# SCH_shield_test_2024-03-10.net
KiCad netlist of a schematic drawn in EasyEDA
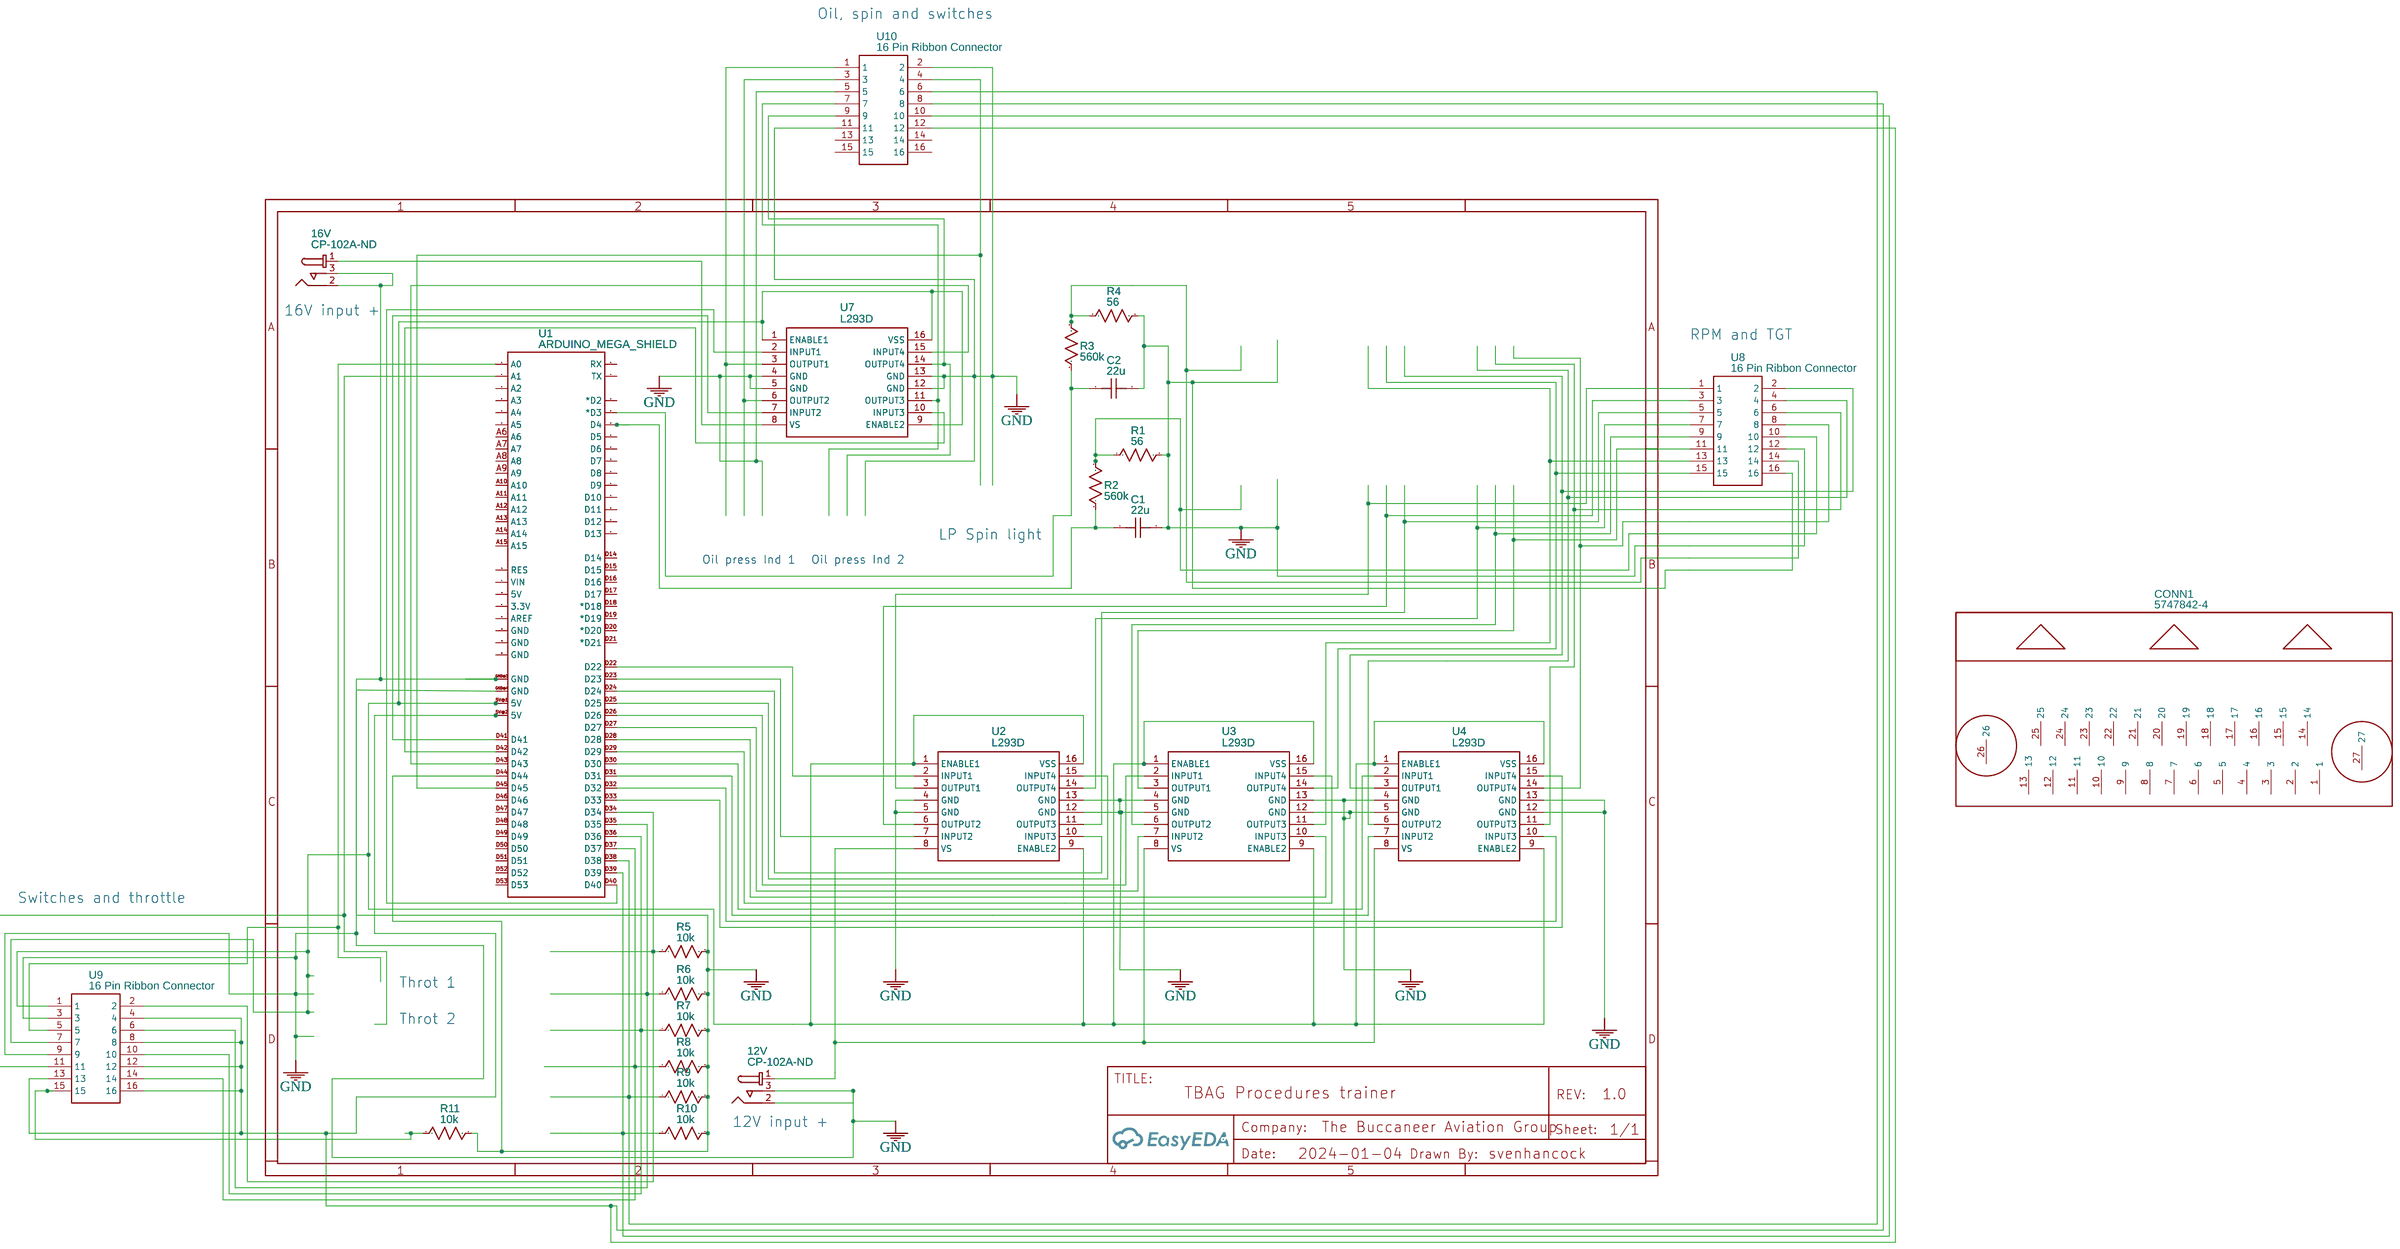
[diagram p0: schematic sheet]

(export (version "E")
  (design (tool "Eeschema 10.0.6"))
  (components
    (comp (ref "12V") (value "CP-102A-ND") (libsource (lib "") (part "CP-102A-ND")))
    (comp (ref "16V") (value "CP-102A-ND") (libsource (lib "") (part "CP-102A-ND_1")))
    (comp (ref "C1") (value "22u") (libsource (lib "") (part "C_0603_US")))
    (comp (ref "C2") (value "22u") (libsource (lib "") (part "C_0603_US")))
    (comp (ref "CONN1") (value "5747842-4") (libsource (lib "") (part "5747842-4")))
    (comp (ref "R1") (value "56") (libsource (lib "") (part "R_0603_US_1")))
    (comp (ref "R2") (value "560k") (libsource (lib "") (part "R_0603_US")))
    (comp (ref "R3") (value "560k") (libsource (lib "") (part "R_0603_US")))
    (comp (ref "R4") (value "56") (libsource (lib "") (part "R_0603_US_1")))
    (comp (ref "R5") (value "10k") (libsource (lib "") (part "R_0603_US_1")))
    (comp (ref "R6") (value "10k") (libsource (lib "") (part "R_0603_US_1")))
    (comp (ref "R7") (value "10k") (libsource (lib "") (part "R_0603_US_1")))
    (comp (ref "R8") (value "10k") (libsource (lib "") (part "R_0603_US_1")))
    (comp (ref "R9") (value "10k") (libsource (lib "") (part "R_0603_US_1")))
    (comp (ref "R10") (value "10k") (libsource (lib "") (part "R_0603_US_1")))
    (comp (ref "R11") (value "10k") (libsource (lib "") (part "R_0603_US_1")))
    (comp (ref "U1") (value "ARDUINO_MEGA_SHIELD") (libsource (lib "") (part "ARDUINO_MEGA_SHIELD")))
    (comp (ref "U2")
      (value "L293D")
      (fields (field (name "Manufacturer") "ST(意法半导体)"))
      (libsource (lib "") (part "L293D"))
    )
    (comp (ref "U3")
      (value "L293D")
      (fields (field (name "Manufacturer") "ST(意法半导体)"))
      (libsource (lib "") (part "L293D"))
    )
    (comp (ref "U4")
      (value "L293D")
      (fields (field (name "Manufacturer") "ST(意法半导体)"))
      (libsource (lib "") (part "L293D"))
    )
    (comp (ref "U7")
      (value "L293D")
      (fields (field (name "Manufacturer") "ST(意法半导体)"))
      (libsource (lib "") (part "L293D"))
    )
    (comp (ref "U8") (value "16 Pin Ribbon Connector") (libsource (lib "") (part "16 Pin Ribbon Connector")))
    (comp (ref "U9") (value "16 Pin Ribbon Connector") (libsource (lib "") (part "16 Pin Ribbon Connector")))
    (comp (ref "U10") (value "16 Pin Ribbon Connector") (libsource (lib "") (part "16 Pin Ribbon Connector")))
  )
  (nets
    (net (code "1") (name "GND") (class "Default")
      (node (ref "12V") (pin "2") (pintype "unspecified"))
      (node (ref "12V") (pin "3") (pintype "unspecified"))
      (node (ref "16V") (pin "2") (pintype "unspecified"))
      (node (ref "16V") (pin "3") (pintype "unspecified"))
      (node (ref "C1") (pin "2") (pinfunction "2_2") (pintype "unspecified"))
      (node (ref "C2") (pin "2") (pinfunction "2_2") (pintype "unspecified"))
      (node (ref "R1") (pin "2") (pinfunction "2_2") (pintype "unspecified"))
      (node (ref "R10") (pin "2") (pinfunction "2_2") (pintype "unspecified"))
      (node (ref "R11") (pin "2") (pinfunction "2_2") (pintype "unspecified"))
      (node (ref "R4") (pin "2") (pinfunction "2_2") (pintype "unspecified"))
      (node (ref "R5") (pin "2") (pinfunction "2_2") (pintype "unspecified"))
      (node (ref "R6") (pin "2") (pinfunction "2_2") (pintype "unspecified"))
      (node (ref "R7") (pin "2") (pinfunction "2_2") (pintype "unspecified"))
      (node (ref "R8") (pin "2") (pinfunction "2_2") (pintype "unspecified"))
      (node (ref "R9") (pin "2") (pinfunction "2_2") (pintype "unspecified"))
      (node (ref "U1") (pin "D44") (pinfunction "D44_D44") (pintype "unspecified"))
      (node (ref "U1") (pin "GND@3") (pinfunction "GND_GND@3") (pintype "unspecified"))
      (node (ref "U10") (pin "11") (pinfunction "11_11") (pintype "unspecified"))
      (node (ref "U10") (pin "2") (pinfunction "2_2") (pintype "unspecified"))
      (node (ref "U10") (pin "5") (pinfunction "5_5") (pintype "unspecified"))
      (node (ref "U2") (pin "12") (pinfunction "GND_12") (pintype "unspecified"))
      (node (ref "U2") (pin "13") (pinfunction "GND_13") (pintype "unspecified"))
      (node (ref "U2") (pin "4") (pinfunction "GND_4") (pintype "unspecified"))
      (node (ref "U2") (pin "5") (pinfunction "GND_5") (pintype "unspecified"))
      (node (ref "U3") (pin "12") (pinfunction "GND_12") (pintype "unspecified"))
      (node (ref "U3") (pin "13") (pinfunction "GND_13") (pintype "unspecified"))
      (node (ref "U3") (pin "4") (pinfunction "GND_4") (pintype "unspecified"))
      (node (ref "U3") (pin "5") (pinfunction "GND_5") (pintype "unspecified"))
      (node (ref "U4") (pin "12") (pinfunction "GND_12") (pintype "unspecified"))
      (node (ref "U4") (pin "13") (pinfunction "GND_13") (pintype "unspecified"))
      (node (ref "U4") (pin "4") (pinfunction "GND_4") (pintype "unspecified"))
      (node (ref "U4") (pin "5") (pinfunction "GND_5") (pintype "unspecified"))
      (node (ref "U7") (pin "12") (pinfunction "GND_12") (pintype "unspecified"))
      (node (ref "U7") (pin "13") (pinfunction "GND_13") (pintype "unspecified"))
      (node (ref "U7") (pin "4") (pinfunction "GND_4") (pintype "unspecified"))
      (node (ref "U7") (pin "5") (pinfunction "GND_5") (pintype "unspecified"))
      (node (ref "U8") (pin "12") (pinfunction "12_12") (pintype "unspecified"))
      (node (ref "U8") (pin "16") (pinfunction "16_16") (pintype "unspecified"))
      (node (ref "U9") (pin "3") (pinfunction "3_3") (pintype "unspecified"))
      (node (ref "U9") (pin "9") (pinfunction "9_9") (pintype "unspecified"))
    )
    (net (code "2") (name "Net-(C1-Pad1)") (class "Default")
      (node (ref "C1") (pin "1") (pinfunction "1_1") (pintype "unspecified"))
      (node (ref "R2") (pin "1") (pinfunction "1_1") (pintype "unspecified"))
      (node (ref "U1") (pin "D4") (pinfunction "D4_D4") (pintype "unspecified"))
    )
    (net (code "3") (name "Net-(R1-Pad1)") (class "Default")
      (node (ref "R1") (pin "1") (pinfunction "1_1") (pintype "unspecified"))
      (node (ref "R2") (pin "2") (pinfunction "2_2") (pintype "unspecified"))
      (node (ref "U8") (pin "10") (pinfunction "10_10") (pintype "unspecified"))
    )
    (net (code "4") (name "Net-(R3-Pad2)") (class "Default")
      (node (ref "R3") (pin "2") (pinfunction "2_2") (pintype "unspecified"))
      (node (ref "R4") (pin "1") (pinfunction "1_1") (pintype "unspecified"))
      (node (ref "U8") (pin "14") (pinfunction "14_14") (pintype "unspecified"))
    )
    (net (code "5") (name "Net-(R5-Pad1)") (class "Default")
      (node (ref "R5") (pin "1") (pinfunction "1_1") (pintype "unspecified"))
      (node (ref "U1") (pin "D34") (pinfunction "D34_D34") (pintype "unspecified"))
      (node (ref "U9") (pin "2") (pinfunction "2_2") (pintype "unspecified"))
    )
    (net (code "6") (name "Net-(R6-Pad1)") (class "Default")
      (node (ref "R6") (pin "1") (pinfunction "1_1") (pintype "unspecified"))
      (node (ref "U1") (pin "D35") (pinfunction "D35_D35") (pintype "unspecified"))
      (node (ref "U9") (pin "6") (pinfunction "6_6") (pintype "unspecified"))
    )
    (net (code "7") (name "Net-(R7-Pad1)") (class "Default")
      (node (ref "R7") (pin "1") (pinfunction "1_1") (pintype "unspecified"))
      (node (ref "U1") (pin "D36") (pinfunction "D36_D36") (pintype "unspecified"))
      (node (ref "U9") (pin "10") (pinfunction "10_10") (pintype "unspecified"))
    )
    (net (code "8") (name "Net-(R8-Pad1)") (class "Default")
      (node (ref "R8") (pin "1") (pinfunction "1_1") (pintype "unspecified"))
      (node (ref "U1") (pin "D37") (pinfunction "D37_D37") (pintype "unspecified"))
      (node (ref "U9") (pin "14") (pinfunction "14_14") (pintype "unspecified"))
    )
    (net (code "9") (name "Net-(R9-Pad1)") (class "Default")
      (node (ref "R9") (pin "1") (pinfunction "1_1") (pintype "unspecified"))
      (node (ref "U1") (pin "D38") (pinfunction "D38_D38") (pintype "unspecified"))
      (node (ref "U10") (pin "6") (pinfunction "6_6") (pintype "unspecified"))
    )
    (net (code "10") (name "Net-(R10-Pad1)") (class "Default")
      (node (ref "R10") (pin "1") (pinfunction "1_1") (pintype "unspecified"))
      (node (ref "U1") (pin "D39") (pinfunction "D39_D39") (pintype "unspecified"))
      (node (ref "U10") (pin "10") (pinfunction "10_10") (pintype "unspecified"))
    )
    (net (code "11") (name "Net-(R11-Pad1)") (class "Default")
      (node (ref "R11") (pin "1") (pinfunction "1_1") (pintype "unspecified"))
      (node (ref "U9") (pin "15") (pinfunction "15_15") (pintype "unspecified"))
    )
    (net (code "12") (name "Net-(U1-*D3)") (class "Default")
      (node (ref "C2") (pin "1") (pinfunction "1_1") (pintype "unspecified"))
      (node (ref "R3") (pin "1") (pinfunction "1_1") (pintype "unspecified"))
      (node (ref "U1") (pin "D3") (pinfunction "*D3_D3") (pintype "unspecified"))
    )
    (net (code "13") (name "Net-(U1-5V-Pad5V@2)") (class "Default")
      (node (ref "U1") (pin "5V@2") (pinfunction "5V_5V@2") (pintype "unspecified"))
      (node (ref "U10") (pin "12") (pinfunction "12_12") (pintype "unspecified"))
      (node (ref "U10") (pin "8") (pinfunction "8_8") (pintype "unspecified"))
      (node (ref "U9") (pin "12") (pinfunction "12_12") (pintype "unspecified"))
      (node (ref "U9") (pin "13") (pinfunction "13_13") (pintype "unspecified"))
      (node (ref "U9") (pin "16") (pinfunction "16_16") (pintype "unspecified"))
      (node (ref "U9") (pin "4") (pinfunction "4_4") (pintype "unspecified"))
      (node (ref "U9") (pin "8") (pinfunction "8_8") (pintype "unspecified"))
    )
    (net (code "14") (name "Net-(U1-PadA0)") (class "Default")
      (node (ref "U1") (pin "A0") (pinfunction "A0_A0") (pintype "unspecified"))
      (node (ref "U9") (pin "5") (pinfunction "5_5") (pintype "unspecified"))
    )
    (net (code "15") (name "Net-(U1-PadA1)") (class "Default")
      (node (ref "U1") (pin "A1") (pinfunction "A1_A1") (pintype "unspecified"))
      (node (ref "U9") (pin "11") (pinfunction "11_11") (pintype "unspecified"))
    )
    (net (code "16") (name "Net-(U1-PadD45)") (class "Default")
      (node (ref "U1") (pin "D45") (pinfunction "D45_D45") (pintype "unspecified"))
      (node (ref "U10") (pin "4") (pinfunction "4_4") (pintype "unspecified"))
    )
    (net (code "17") (name "Net-(U2-ENABLE1)") (class "Default")
      (node (ref "U1") (pin "5V@1") (pinfunction "5V_5V@1") (pintype "unspecified"))
      (node (ref "U2") (pin "1") (pinfunction "ENABLE1_1") (pintype "unspecified"))
      (node (ref "U2") (pin "16") (pinfunction "VSS_16") (pintype "unspecified"))
      (node (ref "U2") (pin "9") (pinfunction "ENABLE2_9") (pintype "unspecified"))
      (node (ref "U3") (pin "1") (pinfunction "ENABLE1_1") (pintype "unspecified"))
      (node (ref "U3") (pin "16") (pinfunction "VSS_16") (pintype "unspecified"))
      (node (ref "U3") (pin "9") (pinfunction "ENABLE2_9") (pintype "unspecified"))
      (node (ref "U4") (pin "1") (pinfunction "ENABLE1_1") (pintype "unspecified"))
      (node (ref "U4") (pin "16") (pinfunction "VSS_16") (pintype "unspecified"))
      (node (ref "U4") (pin "9") (pinfunction "ENABLE2_9") (pintype "unspecified"))
      (node (ref "U7") (pin "1") (pinfunction "ENABLE1_1") (pintype "unspecified"))
      (node (ref "U7") (pin "16") (pinfunction "VSS_16") (pintype "unspecified"))
      (node (ref "U7") (pin "9") (pinfunction "ENABLE2_9") (pintype "unspecified"))
      (node (ref "U9") (pin "1") (pinfunction "1_1") (pintype "unspecified"))
      (node (ref "U9") (pin "7") (pinfunction "7_7") (pintype "unspecified"))
    )
    (net (code "18") (name "Net-(U2-INPUT1)") (class "Default")
      (node (ref "U1") (pin "D22") (pinfunction "D22_D22") (pintype "unspecified"))
      (node (ref "U2") (pin "2") (pinfunction "INPUT1_2") (pintype "unspecified"))
    )
    (net (code "19") (name "Net-(U2-INPUT2)") (class "Default")
      (node (ref "U1") (pin "D23") (pinfunction "D23_D23") (pintype "unspecified"))
      (node (ref "U2") (pin "7") (pinfunction "INPUT2_7") (pintype "unspecified"))
    )
    (net (code "20") (name "Net-(U2-INPUT3)") (class "Default")
      (node (ref "U1") (pin "D24") (pinfunction "D24_D24") (pintype "unspecified"))
      (node (ref "U2") (pin "10") (pinfunction "INPUT3_10") (pintype "unspecified"))
    )
    (net (code "21") (name "Net-(U2-INPUT4)") (class "Default")
      (node (ref "U1") (pin "D25") (pinfunction "D25_D25") (pintype "unspecified"))
      (node (ref "U2") (pin "15") (pinfunction "INPUT4_15") (pintype "unspecified"))
    )
    (net (code "22") (name "Net-(U2-OUTPUT1)") (class "Default")
      (node (ref "U2") (pin "3") (pinfunction "OUTPUT1_3") (pintype "unspecified"))
      (node (ref "U8") (pin "1") (pinfunction "1_1") (pintype "unspecified"))
    )
    (net (code "23") (name "Net-(U2-OUTPUT2)") (class "Default")
      (node (ref "U2") (pin "6") (pinfunction "OUTPUT2_6") (pintype "unspecified"))
      (node (ref "U8") (pin "3") (pinfunction "3_3") (pintype "unspecified"))
    )
    (net (code "24") (name "Net-(U2-OUTPUT3)") (class "Default")
      (node (ref "U2") (pin "11") (pinfunction "OUTPUT3_11") (pintype "unspecified"))
      (node (ref "U8") (pin "5") (pinfunction "5_5") (pintype "unspecified"))
    )
    (net (code "25") (name "Net-(U2-OUTPUT4)") (class "Default")
      (node (ref "U2") (pin "14") (pinfunction "OUTPUT4_14") (pintype "unspecified"))
      (node (ref "U8") (pin "7") (pinfunction "7_7") (pintype "unspecified"))
    )
    (net (code "26") (name "Net-(U2-VS)") (class "Default")
      (node (ref "12V") (pin "1") (pintype "unspecified"))
      (node (ref "U2") (pin "8") (pinfunction "VS_8") (pintype "unspecified"))
      (node (ref "U3") (pin "8") (pinfunction "VS_8") (pintype "unspecified"))
      (node (ref "U4") (pin "8") (pinfunction "VS_8") (pintype "unspecified"))
    )
    (net (code "27") (name "Net-(U3-INPUT1)") (class "Default")
      (node (ref "U1") (pin "D26") (pinfunction "D26_D26") (pintype "unspecified"))
      (node (ref "U3") (pin "2") (pinfunction "INPUT1_2") (pintype "unspecified"))
    )
    (net (code "28") (name "Net-(U3-INPUT2)") (class "Default")
      (node (ref "U1") (pin "D27") (pinfunction "D27_D27") (pintype "unspecified"))
      (node (ref "U3") (pin "7") (pinfunction "INPUT2_7") (pintype "unspecified"))
    )
    (net (code "29") (name "Net-(U3-INPUT3)") (class "Default")
      (node (ref "U1") (pin "D28") (pinfunction "D28_D28") (pintype "unspecified"))
      (node (ref "U3") (pin "10") (pinfunction "INPUT3_10") (pintype "unspecified"))
    )
    (net (code "30") (name "Net-(U3-INPUT4)") (class "Default")
      (node (ref "U1") (pin "D29") (pinfunction "D29_D29") (pintype "unspecified"))
      (node (ref "U3") (pin "15") (pinfunction "INPUT4_15") (pintype "unspecified"))
    )
    (net (code "31") (name "Net-(U3-OUTPUT1)") (class "Default")
      (node (ref "U3") (pin "3") (pinfunction "OUTPUT1_3") (pintype "unspecified"))
      (node (ref "U8") (pin "11") (pinfunction "11_11") (pintype "unspecified"))
    )
    (net (code "32") (name "Net-(U3-OUTPUT2)") (class "Default")
      (node (ref "U3") (pin "6") (pinfunction "OUTPUT2_6") (pintype "unspecified"))
      (node (ref "U8") (pin "9") (pinfunction "9_9") (pintype "unspecified"))
    )
    (net (code "33") (name "Net-(U3-OUTPUT3)") (class "Default")
      (node (ref "U3") (pin "11") (pinfunction "OUTPUT3_11") (pintype "unspecified"))
      (node (ref "U8") (pin "13") (pinfunction "13_13") (pintype "unspecified"))
    )
    (net (code "34") (name "Net-(U3-OUTPUT4)") (class "Default")
      (node (ref "U3") (pin "14") (pinfunction "OUTPUT4_14") (pintype "unspecified"))
      (node (ref "U8") (pin "15") (pinfunction "15_15") (pintype "unspecified"))
    )
    (net (code "35") (name "Net-(U4-INPUT1)") (class "Default")
      (node (ref "U1") (pin "D30") (pinfunction "D30_D30") (pintype "unspecified"))
      (node (ref "U4") (pin "2") (pinfunction "INPUT1_2") (pintype "unspecified"))
    )
    (net (code "36") (name "Net-(U4-INPUT2)") (class "Default")
      (node (ref "U1") (pin "D31") (pinfunction "D31_D31") (pintype "unspecified"))
      (node (ref "U4") (pin "7") (pinfunction "INPUT2_7") (pintype "unspecified"))
    )
    (net (code "37") (name "Net-(U4-INPUT3)") (class "Default")
      (node (ref "U1") (pin "D32") (pinfunction "D32_D32") (pintype "unspecified"))
      (node (ref "U4") (pin "10") (pinfunction "INPUT3_10") (pintype "unspecified"))
    )
    (net (code "38") (name "Net-(U4-INPUT4)") (class "Default")
      (node (ref "U1") (pin "D33") (pinfunction "D33_D33") (pintype "unspecified"))
      (node (ref "U4") (pin "15") (pinfunction "INPUT4_15") (pintype "unspecified"))
    )
    (net (code "39") (name "Net-(U4-OUTPUT1)") (class "Default")
      (node (ref "U4") (pin "3") (pinfunction "OUTPUT1_3") (pintype "unspecified"))
      (node (ref "U8") (pin "2") (pinfunction "2_2") (pintype "unspecified"))
    )
    (net (code "40") (name "Net-(U4-OUTPUT2)") (class "Default")
      (node (ref "U4") (pin "6") (pinfunction "OUTPUT2_6") (pintype "unspecified"))
      (node (ref "U8") (pin "4") (pinfunction "4_4") (pintype "unspecified"))
    )
    (net (code "41") (name "Net-(U4-OUTPUT3)") (class "Default")
      (node (ref "U4") (pin "11") (pinfunction "OUTPUT3_11") (pintype "unspecified"))
      (node (ref "U8") (pin "6") (pinfunction "6_6") (pintype "unspecified"))
    )
    (net (code "42") (name "Net-(U4-OUTPUT4)") (class "Default")
      (node (ref "U4") (pin "14") (pinfunction "OUTPUT4_14") (pintype "unspecified"))
      (node (ref "U8") (pin "8") (pinfunction "8_8") (pintype "unspecified"))
    )
    (net (code "43") (name "Net-(U7-INPUT1)") (class "Default")
      (node (ref "U1") (pin "D40") (pinfunction "D40_D40") (pintype "unspecified"))
      (node (ref "U7") (pin "2") (pinfunction "INPUT1_2") (pintype "unspecified"))
    )
    (net (code "44") (name "Net-(U7-INPUT2)") (class "Default")
      (node (ref "U1") (pin "D41") (pinfunction "D41_D41") (pintype "unspecified"))
      (node (ref "U7") (pin "7") (pinfunction "INPUT2_7") (pintype "unspecified"))
    )
    (net (code "45") (name "Net-(U7-INPUT3)") (class "Default")
      (node (ref "U1") (pin "D42") (pinfunction "D42_D42") (pintype "unspecified"))
      (node (ref "U7") (pin "10") (pinfunction "INPUT3_10") (pintype "unspecified"))
    )
    (net (code "46") (name "Net-(U7-INPUT4)") (class "Default")
      (node (ref "U1") (pin "D43") (pinfunction "D43_D43") (pintype "unspecified"))
      (node (ref "U7") (pin "15") (pinfunction "INPUT4_15") (pintype "unspecified"))
    )
    (net (code "47") (name "Net-(U7-OUTPUT1)") (class "Default")
      (node (ref "U10") (pin "1") (pinfunction "1_1") (pintype "unspecified"))
      (node (ref "U7") (pin "3") (pinfunction "OUTPUT1_3") (pintype "unspecified"))
    )
    (net (code "48") (name "Net-(U7-OUTPUT2)") (class "Default")
      (node (ref "U10") (pin "3") (pinfunction "3_3") (pintype "unspecified"))
      (node (ref "U7") (pin "6") (pinfunction "OUTPUT2_6") (pintype "unspecified"))
    )
    (net (code "49") (name "Net-(U7-OUTPUT3)") (class "Default")
      (node (ref "U10") (pin "7") (pinfunction "7_7") (pintype "unspecified"))
      (node (ref "U7") (pin "11") (pinfunction "OUTPUT3_11") (pintype "unspecified"))
    )
    (net (code "50") (name "Net-(U7-OUTPUT4)") (class "Default")
      (node (ref "U10") (pin "9") (pinfunction "9_9") (pintype "unspecified"))
      (node (ref "U7") (pin "14") (pinfunction "OUTPUT4_14") (pintype "unspecified"))
    )
    (net (code "51") (name "Net-(U7-VS)") (class "Default")
      (node (ref "16V") (pin "1") (pintype "unspecified"))
      (node (ref "U7") (pin "8") (pinfunction "VS_8") (pintype "unspecified"))
    )
    (net (code "52") (name "unconnected-(CONN1-Pad1)") (class "Default")
      (node (ref "CONN1") (pin "1") (pinfunction "1_1") (pintype "unspecified"))
    )
    (net (code "53") (name "unconnected-(CONN1-Pad2)") (class "Default")
      (node (ref "CONN1") (pin "2") (pinfunction "2_2") (pintype "unspecified"))
    )
    (net (code "54") (name "unconnected-(CONN1-Pad3)") (class "Default")
      (node (ref "CONN1") (pin "3") (pinfunction "3_3") (pintype "unspecified"))
    )
    (net (code "55") (name "unconnected-(CONN1-Pad4)") (class "Default")
      (node (ref "CONN1") (pin "4") (pinfunction "4_4") (pintype "unspecified"))
    )
    (net (code "56") (name "unconnected-(CONN1-Pad5)") (class "Default")
      (node (ref "CONN1") (pin "5") (pinfunction "5_5") (pintype "unspecified"))
    )
    (net (code "57") (name "unconnected-(CONN1-Pad6)") (class "Default")
      (node (ref "CONN1") (pin "6") (pinfunction "6_6") (pintype "unspecified"))
    )
    (net (code "58") (name "unconnected-(CONN1-Pad7)") (class "Default")
      (node (ref "CONN1") (pin "7") (pinfunction "7_7") (pintype "unspecified"))
    )
    (net (code "59") (name "unconnected-(CONN1-Pad8)") (class "Default")
      (node (ref "CONN1") (pin "8") (pinfunction "8_8") (pintype "unspecified"))
    )
    (net (code "60") (name "unconnected-(CONN1-Pad9)") (class "Default")
      (node (ref "CONN1") (pin "9") (pinfunction "9_9") (pintype "unspecified"))
    )
    (net (code "61") (name "unconnected-(CONN1-Pad10)") (class "Default")
      (node (ref "CONN1") (pin "10") (pinfunction "10_10") (pintype "unspecified"))
    )
    (net (code "62") (name "unconnected-(CONN1-Pad11)") (class "Default")
      (node (ref "CONN1") (pin "11") (pinfunction "11_11") (pintype "unspecified"))
    )
    (net (code "63") (name "unconnected-(CONN1-Pad12)") (class "Default")
      (node (ref "CONN1") (pin "12") (pinfunction "12_12") (pintype "unspecified"))
    )
    (net (code "64") (name "unconnected-(CONN1-Pad13)") (class "Default")
      (node (ref "CONN1") (pin "13") (pinfunction "13_13") (pintype "unspecified"))
    )
    (net (code "65") (name "unconnected-(CONN1-Pad14)") (class "Default")
      (node (ref "CONN1") (pin "14") (pinfunction "14_14") (pintype "unspecified"))
    )
    (net (code "66") (name "unconnected-(CONN1-Pad15)") (class "Default")
      (node (ref "CONN1") (pin "15") (pinfunction "15_15") (pintype "unspecified"))
    )
    (net (code "67") (name "unconnected-(CONN1-Pad16)") (class "Default")
      (node (ref "CONN1") (pin "16") (pinfunction "16_16") (pintype "unspecified"))
    )
    (net (code "68") (name "unconnected-(CONN1-Pad17)") (class "Default")
      (node (ref "CONN1") (pin "17") (pinfunction "17_17") (pintype "unspecified"))
    )
    (net (code "69") (name "unconnected-(CONN1-Pad18)") (class "Default")
      (node (ref "CONN1") (pin "18") (pinfunction "18_18") (pintype "unspecified"))
    )
    (net (code "70") (name "unconnected-(CONN1-Pad19)") (class "Default")
      (node (ref "CONN1") (pin "19") (pinfunction "19_19") (pintype "unspecified"))
    )
    (net (code "71") (name "unconnected-(CONN1-Pad20)") (class "Default")
      (node (ref "CONN1") (pin "20") (pinfunction "20_20") (pintype "unspecified"))
    )
    (net (code "72") (name "unconnected-(CONN1-Pad21)") (class "Default")
      (node (ref "CONN1") (pin "21") (pinfunction "21_21") (pintype "unspecified"))
    )
    (net (code "73") (name "unconnected-(CONN1-Pad22)") (class "Default")
      (node (ref "CONN1") (pin "22") (pinfunction "22_22") (pintype "unspecified"))
    )
    (net (code "74") (name "unconnected-(CONN1-Pad23)") (class "Default")
      (node (ref "CONN1") (pin "23") (pinfunction "23_23") (pintype "unspecified"))
    )
    (net (code "75") (name "unconnected-(CONN1-Pad24)") (class "Default")
      (node (ref "CONN1") (pin "24") (pinfunction "24_24") (pintype "unspecified"))
    )
    (net (code "76") (name "unconnected-(CONN1-Pad25)") (class "Default")
      (node (ref "CONN1") (pin "25") (pinfunction "25_25") (pintype "unspecified"))
    )
    (net (code "77") (name "unconnected-(CONN1-Pad26)") (class "Default")
      (node (ref "CONN1") (pin "26") (pinfunction "26_26") (pintype "unspecified"))
    )
    (net (code "78") (name "unconnected-(CONN1-Pad27)") (class "Default")
      (node (ref "CONN1") (pin "27") (pinfunction "27_27") (pintype "unspecified"))
    )
    (net (code "79") (name "unconnected-(U1-*D2-PadD2)") (class "Default")
      (node (ref "U1") (pin "D2") (pinfunction "*D2_D2") (pintype "unspecified"))
    )
    (net (code "80") (name "unconnected-(U1-*D18-PadD18)") (class "Default")
      (node (ref "U1") (pin "D18") (pinfunction "*D18_D18") (pintype "unspecified"))
    )
    (net (code "81") (name "unconnected-(U1-*D19-PadD19)") (class "Default")
      (node (ref "U1") (pin "D19") (pinfunction "*D19_D19") (pintype "unspecified"))
    )
    (net (code "82") (name "unconnected-(U1-*D20-PadD20)") (class "Default")
      (node (ref "U1") (pin "D20") (pinfunction "*D20_D20") (pintype "unspecified"))
    )
    (net (code "83") (name "unconnected-(U1-*D21-PadD21)") (class "Default")
      (node (ref "U1") (pin "D21") (pinfunction "*D21_D21") (pintype "unspecified"))
    )
    (net (code "84") (name "unconnected-(U1-5V-Pad5V@0)") (class "Default")
      (node (ref "U1") (pin "5V@0") (pinfunction "5V_5V@0") (pintype "passive"))
    )
    (net (code "85") (name "unconnected-(U1-GND-PadGND@0)") (class "Default")
      (node (ref "U1") (pin "GND@0") (pinfunction "GND_GND@0") (pintype "unspecified"))
    )
    (net (code "86") (name "unconnected-(U1-GND-PadGND@1)") (class "Default")
      (node (ref "U1") (pin "GND@1") (pinfunction "GND_GND@1") (pintype "unspecified"))
    )
    (net (code "87") (name "unconnected-(U1-GND-PadGND@2)") (class "Default")
      (node (ref "U1") (pin "GND@2") (pinfunction "GND_GND@2") (pintype "unspecified"))
    )
    (net (code "88") (name "unconnected-(U1-GND-PadGND@4)") (class "Default")
      (node (ref "U1") (pin "GND@4") (pinfunction "GND_GND@4") (pintype "unspecified"))
    )
    (net (code "89") (name "unconnected-(U1-Pad3.3V)") (class "Default")
      (node (ref "U1") (pin "3.3V") (pinfunction "3.3V_3.3V") (pintype "unspecified"))
    )
    (net (code "90") (name "unconnected-(U1-PadA2)") (class "Default")
      (node (ref "U1") (pin "A2") (pinfunction "A2_A2") (pintype "unspecified"))
    )
    (net (code "91") (name "unconnected-(U1-PadA3)") (class "Default")
      (node (ref "U1") (pin "A3") (pinfunction "A3_A3") (pintype "unspecified"))
    )
    (net (code "92") (name "unconnected-(U1-PadA4)") (class "Default")
      (node (ref "U1") (pin "A4") (pinfunction "A4_A4") (pintype "unspecified"))
    )
    (net (code "93") (name "unconnected-(U1-PadA5)") (class "Default")
      (node (ref "U1") (pin "A5") (pinfunction "A5_A5") (pintype "unspecified"))
    )
    (net (code "94") (name "unconnected-(U1-PadA6)") (class "Default")
      (node (ref "U1") (pin "A6") (pinfunction "A6_A6") (pintype "unspecified"))
    )
    (net (code "95") (name "unconnected-(U1-PadA7)") (class "Default")
      (node (ref "U1") (pin "A7") (pinfunction "A7_A7") (pintype "unspecified"))
    )
    (net (code "96") (name "unconnected-(U1-PadA8)") (class "Default")
      (node (ref "U1") (pin "A8") (pinfunction "A8_A8") (pintype "unspecified"))
    )
    (net (code "97") (name "unconnected-(U1-PadA9)") (class "Default")
      (node (ref "U1") (pin "A9") (pinfunction "A9_A9") (pintype "unspecified"))
    )
    (net (code "98") (name "unconnected-(U1-PadA10)") (class "Default")
      (node (ref "U1") (pin "A10") (pinfunction "A10_A10") (pintype "unspecified"))
    )
    (net (code "99") (name "unconnected-(U1-PadA11)") (class "Default")
      (node (ref "U1") (pin "A11") (pinfunction "A11_A11") (pintype "unspecified"))
    )
    (net (code "100") (name "unconnected-(U1-PadA12)") (class "Default")
      (node (ref "U1") (pin "A12") (pinfunction "A12_A12") (pintype "unspecified"))
    )
    (net (code "101") (name "unconnected-(U1-PadA13)") (class "Default")
      (node (ref "U1") (pin "A13") (pinfunction "A13_A13") (pintype "unspecified"))
    )
    (net (code "102") (name "unconnected-(U1-PadA14)") (class "Default")
      (node (ref "U1") (pin "A14") (pinfunction "A14_A14") (pintype "unspecified"))
    )
    (net (code "103") (name "unconnected-(U1-PadA15)") (class "Default")
      (node (ref "U1") (pin "A15") (pinfunction "A15_A15") (pintype "unspecified"))
    )
    (net (code "104") (name "unconnected-(U1-PadAREF)") (class "Default")
      (node (ref "U1") (pin "AREF") (pinfunction "AREF_AREF") (pintype "unspecified"))
    )
    (net (code "105") (name "unconnected-(U1-PadD5)") (class "Default")
      (node (ref "U1") (pin "D5") (pinfunction "D5_D5") (pintype "unspecified"))
    )
    (net (code "106") (name "unconnected-(U1-PadD6)") (class "Default")
      (node (ref "U1") (pin "D6") (pinfunction "D6_D6") (pintype "unspecified"))
    )
    (net (code "107") (name "unconnected-(U1-PadD7)") (class "Default")
      (node (ref "U1") (pin "D7") (pinfunction "D7_D7") (pintype "unspecified"))
    )
    (net (code "108") (name "unconnected-(U1-PadD8)") (class "Default")
      (node (ref "U1") (pin "D8") (pinfunction "D8_D8") (pintype "unspecified"))
    )
    (net (code "109") (name "unconnected-(U1-PadD9)") (class "Default")
      (node (ref "U1") (pin "D9") (pinfunction "D9_D9") (pintype "unspecified"))
    )
    (net (code "110") (name "unconnected-(U1-PadD10)") (class "Default")
      (node (ref "U1") (pin "D10") (pinfunction "D10_D10") (pintype "unspecified"))
    )
    (net (code "111") (name "unconnected-(U1-PadD11)") (class "Default")
      (node (ref "U1") (pin "D11") (pinfunction "D11_D11") (pintype "unspecified"))
    )
    (net (code "112") (name "unconnected-(U1-PadD12)") (class "Default")
      (node (ref "U1") (pin "D12") (pinfunction "D12_D12") (pintype "unspecified"))
    )
    (net (code "113") (name "unconnected-(U1-PadD13)") (class "Default")
      (node (ref "U1") (pin "D13") (pinfunction "D13_D13") (pintype "unspecified"))
    )
    (net (code "114") (name "unconnected-(U1-PadD14)") (class "Default")
      (node (ref "U1") (pin "D14") (pinfunction "D14_D14") (pintype "unspecified"))
    )
    (net (code "115") (name "unconnected-(U1-PadD15)") (class "Default")
      (node (ref "U1") (pin "D15") (pinfunction "D15_D15") (pintype "unspecified"))
    )
    (net (code "116") (name "unconnected-(U1-PadD16)") (class "Default")
      (node (ref "U1") (pin "D16") (pinfunction "D16_D16") (pintype "unspecified"))
    )
    (net (code "117") (name "unconnected-(U1-PadD17)") (class "Default")
      (node (ref "U1") (pin "D17") (pinfunction "D17_D17") (pintype "unspecified"))
    )
    (net (code "118") (name "unconnected-(U1-PadD46)") (class "Default")
      (node (ref "U1") (pin "D46") (pinfunction "D46_D46") (pintype "unspecified"))
    )
    (net (code "119") (name "unconnected-(U1-PadD47)") (class "Default")
      (node (ref "U1") (pin "D47") (pinfunction "D47_D47") (pintype "unspecified"))
    )
    (net (code "120") (name "unconnected-(U1-PadD48)") (class "Default")
      (node (ref "U1") (pin "D48") (pinfunction "D48_D48") (pintype "unspecified"))
    )
    (net (code "121") (name "unconnected-(U1-PadD49)") (class "Default")
      (node (ref "U1") (pin "D49") (pinfunction "D49_D49") (pintype "unspecified"))
    )
    (net (code "122") (name "unconnected-(U1-PadD50)") (class "Default")
      (node (ref "U1") (pin "D50") (pinfunction "D50_D50") (pintype "unspecified"))
    )
    (net (code "123") (name "unconnected-(U1-PadD51)") (class "Default")
      (node (ref "U1") (pin "D51") (pinfunction "D51_D51") (pintype "unspecified"))
    )
    (net (code "124") (name "unconnected-(U1-PadD52)") (class "Default")
      (node (ref "U1") (pin "D52") (pinfunction "D52_D52") (pintype "unspecified"))
    )
    (net (code "125") (name "unconnected-(U1-PadD53)") (class "Default")
      (node (ref "U1") (pin "D53") (pinfunction "D53_D53") (pintype "unspecified"))
    )
    (net (code "126") (name "unconnected-(U1-PadRES)") (class "Default")
      (node (ref "U1") (pin "RES") (pinfunction "RES_RES") (pintype "unspecified"))
    )
    (net (code "127") (name "unconnected-(U1-PadRX)") (class "Default")
      (node (ref "U1") (pin "RX") (pinfunction "RX_RX") (pintype "unspecified"))
    )
    (net (code "128") (name "unconnected-(U1-PadTX)") (class "Default")
      (node (ref "U1") (pin "TX") (pinfunction "TX_TX") (pintype "unspecified"))
    )
    (net (code "129") (name "unconnected-(U1-PadVIN)") (class "Default")
      (node (ref "U1") (pin "VIN") (pinfunction "VIN_VIN") (pintype "unspecified"))
    )
    (net (code "130") (name "unconnected-(U10-Pad13)") (class "Default")
      (node (ref "U10") (pin "13") (pinfunction "13_13") (pintype "unspecified"))
    )
    (net (code "131") (name "unconnected-(U10-Pad14)") (class "Default")
      (node (ref "U10") (pin "14") (pinfunction "14_14") (pintype "unspecified"))
    )
    (net (code "132") (name "unconnected-(U10-Pad15)") (class "Default")
      (node (ref "U10") (pin "15") (pinfunction "15_15") (pintype "unspecified"))
    )
    (net (code "133") (name "unconnected-(U10-Pad16)") (class "Default")
      (node (ref "U10") (pin "16") (pinfunction "16_16") (pintype "unspecified"))
    )
  )
)
